# Politeitonsirene_V1.net
KiCad netlist of a schematic drawn in EAGLE
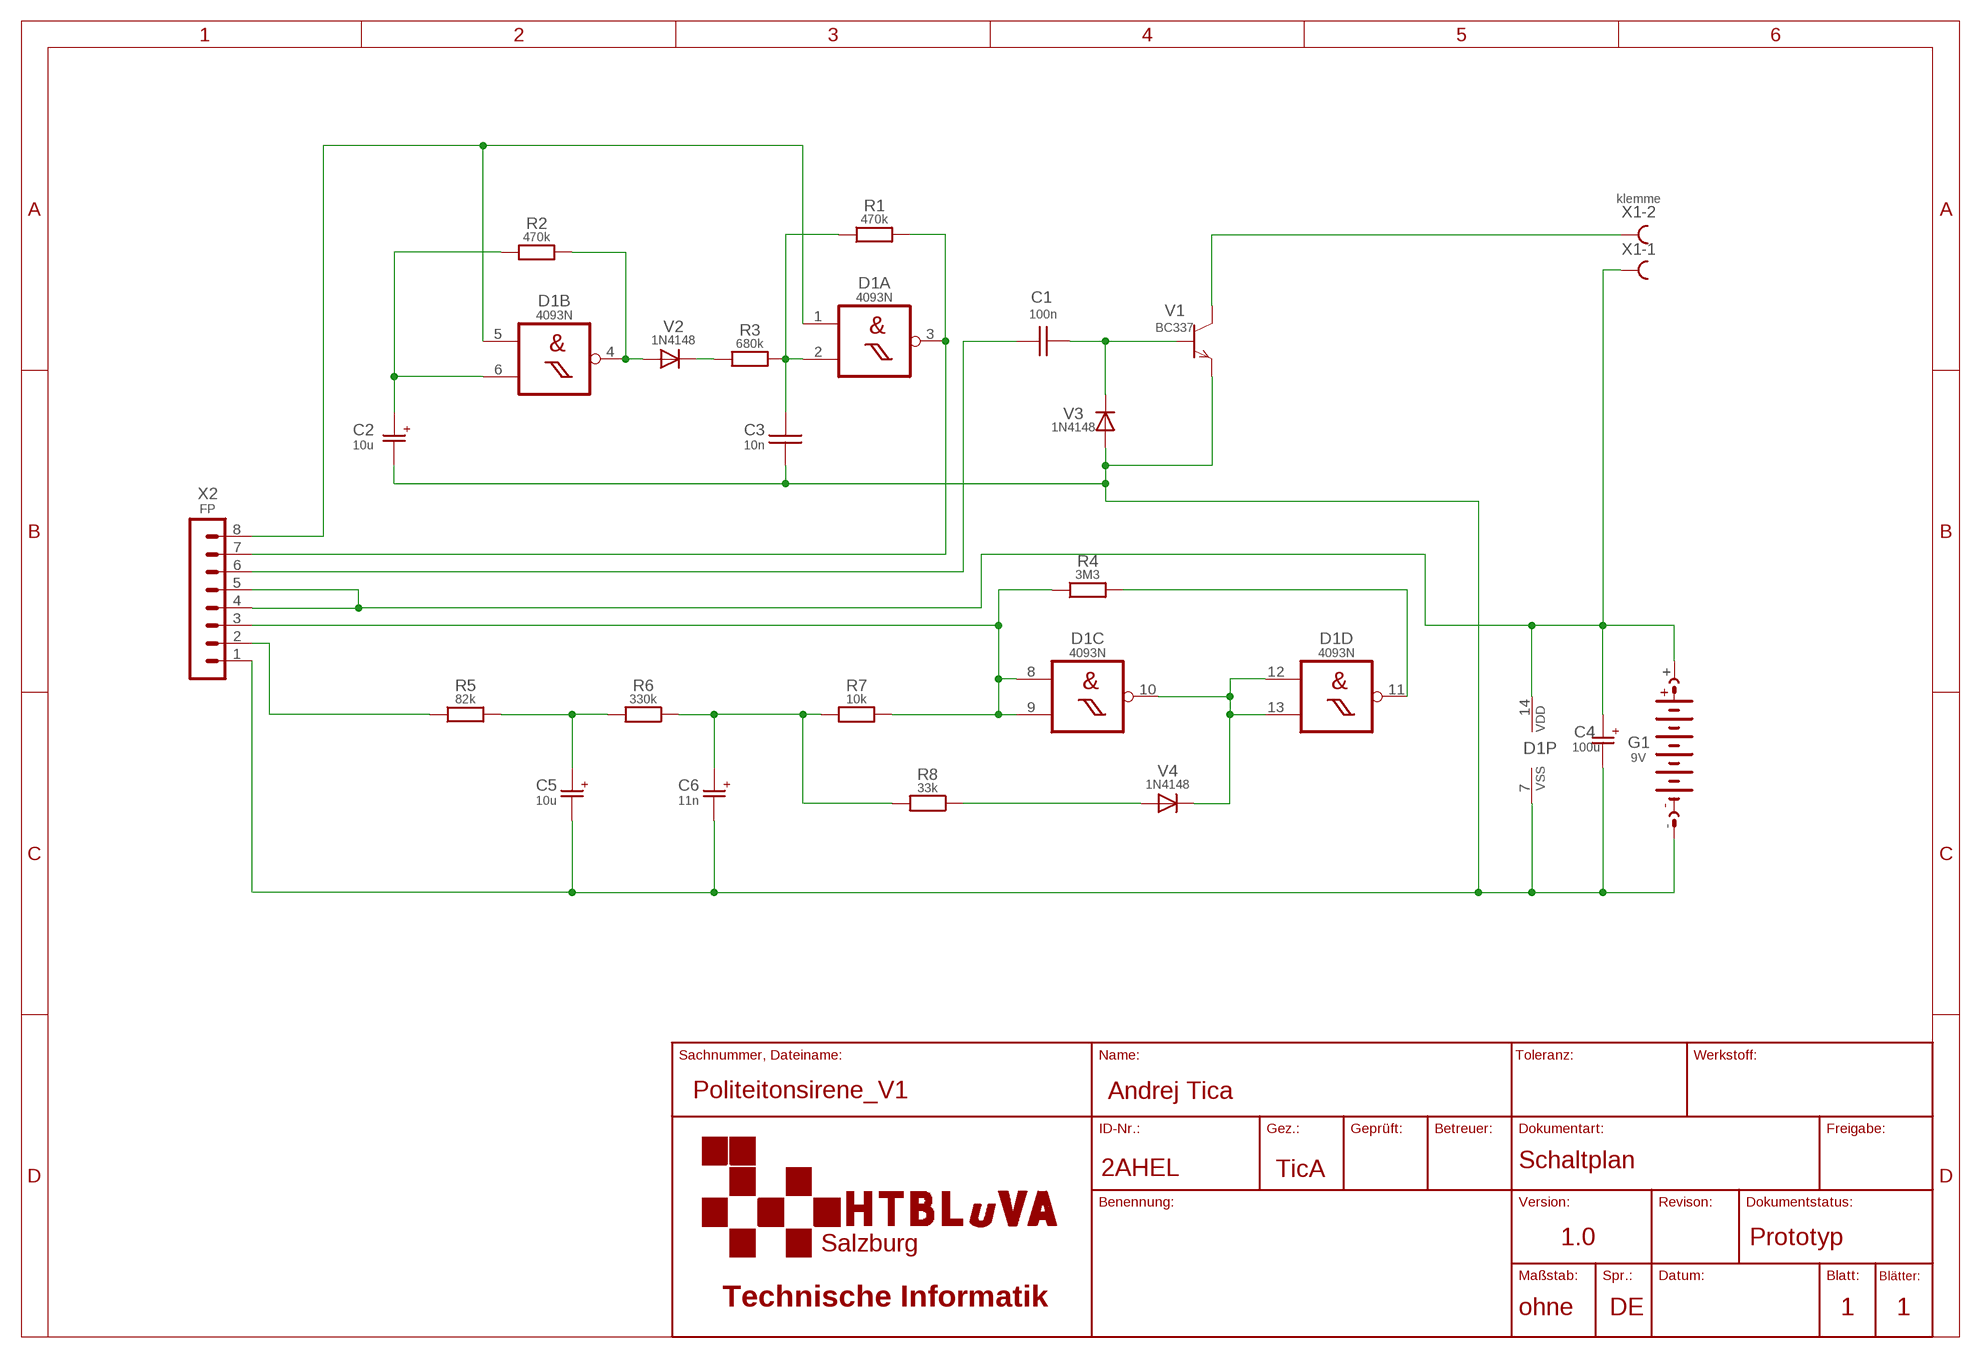
[diagram p0: schematic, sheet 1]

(export (version "E")
  (design (tool "Eeschema 10.0.6"))
  (components
    (comp (ref "C1")
      (value "100n")
      (footprint "eagle-import:C1206")
      (libsource (lib "eagle-import") (part "C-V_C1206"))
    )
    (comp (ref "C2")
      (value "10u")
      (footprint "eagle-import:E2,5-5")
      (libsource (lib "eagle-import") (part "CPOL-V_E2.5-5"))
    )
    (comp (ref "C3")
      (value "10n")
      (footprint "eagle-import:C050-024X044")
      (libsource (lib "eagle-import") (part "rcl_TicA_C-V_050-024X044"))
    )
    (comp (ref "C4")
      (value "100u")
      (footprint "eagle-import:E2,5-6")
      (libsource (lib "eagle-import") (part "CPOL-V_E2.5-6"))
    )
    (comp (ref "C5")
      (value "10u")
      (footprint "eagle-import:E2,5-5")
      (libsource (lib "eagle-import") (part "CPOL-V_E2.5-5"))
    )
    (comp (ref "C6")
      (value "11n")
      (footprint "eagle-import:E2,5-5")
      (libsource (lib "eagle-import") (part "CPOL-V_E2.5-5"))
    )
    (comp (ref "D1")
      (value "4093N")
      (footprint "eagle-import:DIL14")
      (libsource (lib "eagle-import") (part "4093N"))
    )
    (comp (ref "G1")
      (value "9V")
      (footprint "eagle-import:AB9V")
      (libsource (lib "eagle-import") (part "BATCLIP-9V-V_9V"))
    )
    (comp (ref "R1")
      (value "470k")
      (footprint "eagle-import:R2512")
      (libsource (lib "eagle-import") (part "R-H_R2512"))
    )
    (comp (ref "R2")
      (value "470k")
      (footprint "eagle-import:R2512")
      (libsource (lib "eagle-import") (part "R-H_R2512"))
    )
    (comp (ref "R3")
      (value "680k")
      (footprint "eagle-import:R2512")
      (libsource (lib "eagle-import") (part "R-H_R2512"))
    )
    (comp (ref "R4")
      (value "3M3")
      (footprint "eagle-import:R2512")
      (libsource (lib "eagle-import") (part "R-H_R2512"))
    )
    (comp (ref "R5")
      (value "82k")
      (footprint "eagle-import:R2512")
      (libsource (lib "eagle-import") (part "R-H_R2512"))
    )
    (comp (ref "R6")
      (value "330k")
      (footprint "eagle-import:R2512")
      (libsource (lib "eagle-import") (part "R-H_R2512"))
    )
    (comp (ref "R7")
      (value "10k")
      (footprint "eagle-import:R2512")
      (libsource (lib "eagle-import") (part "R-H_R2512"))
    )
    (comp (ref "R8")
      (value "33k")
      (footprint "eagle-import:R2512")
      (libsource (lib "eagle-import") (part "R-H_R2512"))
    )
    (comp (ref "V1")
      (value "BC337")
      (footprint "eagle-import:TO92")
      (libsource (lib "eagle-import") (part "BC337"))
    )
    (comp (ref "V2")
      (value "1N4148")
      (footprint "eagle-import:DO35-7")
      (libsource (lib "eagle-import") (part "1N4148_DO35-7"))
    )
    (comp (ref "V3")
      (value "1N4148")
      (footprint "eagle-import:DO35-7")
      (libsource (lib "eagle-import") (part "1N4148_DO35-7"))
    )
    (comp (ref "V4")
      (value "1N4148")
      (footprint "eagle-import:DO35-7")
      (libsource (lib "eagle-import") (part "1N4148_DO35-7"))
    )
    (comp (ref "X1")
      (value "klemme")
      (footprint "eagle-import:AK500_2")
      (libsource (lib "eagle-import") (part "AK500/2"))
    )
    (comp (ref "X2")
      (value "FP")
      (footprint "eagle-import:MA08-1")
      (libsource (lib "eagle-import") (part "MA08-1"))
    )
  )
  (nets
    (net (code "1") (name "Net-(C1-Pad2)") (class "Default")
      (node (ref "C1") (pin "2") (pinfunction "2_2") (pintype "passive"))
      (node (ref "X2") (pin "6") (pinfunction "6_6") (pintype "passive"))
    )
    (net (code "2") (name "Net-(C5-Pad+)") (class "Default")
      (node (ref "C5") (pin "+") (pinfunction "+_+") (pintype "passive"))
      (node (ref "R5") (pin "2") (pinfunction "2_2") (pintype "passive"))
      (node (ref "R6") (pin "2") (pinfunction "2_2") (pintype "passive"))
    )
    (net (code "3") (name "Net-(C6-Pad+)") (class "Default")
      (node (ref "C6") (pin "+") (pinfunction "+_+") (pintype "passive"))
      (node (ref "R6") (pin "1") (pinfunction "1_1") (pintype "passive"))
      (node (ref "R7") (pin "2") (pinfunction "2_2") (pintype "passive"))
      (node (ref "R8") (pin "2") (pinfunction "2_2") (pintype "passive"))
    )
    (net (code "4") (name "Net-(D1A-I0)") (class "Default")
      (node (ref "D1") (pin "1") (pinfunction "I0_1") (pintype "input"))
      (node (ref "D1") (pin "5") (pinfunction "I0_5") (pintype "input"))
      (node (ref "X2") (pin "8") (pinfunction "8_8") (pintype "passive"))
    )
    (net (code "5") (name "Net-(D1A-I1)") (class "Default")
      (node (ref "C3") (pin "1") (pinfunction "1_1") (pintype "passive"))
      (node (ref "D1") (pin "2") (pinfunction "I1_2") (pintype "input"))
      (node (ref "R1") (pin "1") (pinfunction "1_1") (pintype "passive"))
      (node (ref "R3") (pin "2") (pinfunction "2_2") (pintype "passive"))
    )
    (net (code "6") (name "Net-(D1A-O)") (class "Default")
      (node (ref "D1") (pin "3") (pinfunction "O_3") (pintype "output"))
      (node (ref "R1") (pin "2") (pinfunction "2_2") (pintype "passive"))
      (node (ref "X2") (pin "7") (pinfunction "7_7") (pintype "passive"))
    )
    (net (code "7") (name "Net-(D1B-I1)") (class "Default")
      (node (ref "C2") (pin "+") (pinfunction "+_+") (pintype "passive"))
      (node (ref "D1") (pin "6") (pinfunction "I1_6") (pintype "input"))
      (node (ref "R2") (pin "1") (pinfunction "1_1") (pintype "passive"))
    )
    (net (code "8") (name "Net-(D1B-O)") (class "Default")
      (node (ref "D1") (pin "4") (pinfunction "O_4") (pintype "output"))
      (node (ref "R2") (pin "2") (pinfunction "2_2") (pintype "passive"))
      (node (ref "V2") (pin "A") (pinfunction "A_A") (pintype "passive"))
    )
    (net (code "9") (name "Net-(D1C-I0)") (class "Default")
      (node (ref "D1") (pin "8") (pinfunction "I0_8") (pintype "input"))
      (node (ref "D1") (pin "9") (pinfunction "I1_9") (pintype "input"))
      (node (ref "R4") (pin "1") (pinfunction "1_1") (pintype "passive"))
      (node (ref "R7") (pin "1") (pinfunction "1_1") (pintype "passive"))
      (node (ref "X2") (pin "3") (pinfunction "3_3") (pintype "passive"))
    )
    (net (code "10") (name "Net-(D1C-O)") (class "Default")
      (node (ref "D1") (pin "10") (pinfunction "O_10") (pintype "output"))
      (node (ref "D1") (pin "12") (pinfunction "I0_12") (pintype "input"))
      (node (ref "D1") (pin "13") (pinfunction "I1_13") (pintype "input"))
      (node (ref "V4") (pin "C") (pinfunction "C_C") (pintype "passive"))
    )
    (net (code "11") (name "Net-(D1D-O)") (class "Default")
      (node (ref "D1") (pin "11") (pinfunction "O_11") (pintype "output"))
      (node (ref "R4") (pin "2") (pinfunction "2_2") (pintype "passive"))
    )
    (net (code "12") (name "Net-(D1E-VDD)") (class "Default")
      (node (ref "C4") (pin "+") (pinfunction "+_+") (pintype "passive"))
      (node (ref "D1") (pin "14") (pinfunction "VDD_14") (pintype "power_in"))
      (node (ref "G1") (pin "+") (pinfunction "+_+") (pintype "passive"))
      (node (ref "X1") (pin "1") (pinfunction "KL_1") (pintype "passive"))
      (node (ref "X2") (pin "4") (pinfunction "4_4") (pintype "passive"))
      (node (ref "X2") (pin "5") (pinfunction "5_5") (pintype "passive"))
    )
    (net (code "13") (name "Net-(D1E-VSS)") (class "Default")
      (node (ref "C2") (pin "-") (pinfunction "-_-") (pintype "passive"))
      (node (ref "C3") (pin "2") (pinfunction "2_2") (pintype "passive"))
      (node (ref "C4") (pin "-") (pinfunction "-_-") (pintype "passive"))
      (node (ref "C5") (pin "-") (pinfunction "-_-") (pintype "passive"))
      (node (ref "C6") (pin "-") (pinfunction "-_-") (pintype "passive"))
      (node (ref "D1") (pin "7") (pinfunction "VSS_7") (pintype "power_in"))
      (node (ref "G1") (pin "-") (pinfunction "-_-") (pintype "passive"))
      (node (ref "V1") (pin "1") (pinfunction "E_1") (pintype "passive"))
      (node (ref "V3") (pin "A") (pinfunction "A_A") (pintype "passive"))
      (node (ref "X2") (pin "1") (pinfunction "1_1") (pintype "passive"))
    )
    (net (code "14") (name "Net-(R3-Pad1)") (class "Default")
      (node (ref "R3") (pin "1") (pinfunction "1_1") (pintype "passive"))
      (node (ref "V2") (pin "C") (pinfunction "C_C") (pintype "passive"))
    )
    (net (code "15") (name "Net-(R5-Pad1)") (class "Default")
      (node (ref "R5") (pin "1") (pinfunction "1_1") (pintype "passive"))
      (node (ref "X2") (pin "2") (pinfunction "2_2") (pintype "passive"))
    )
    (net (code "16") (name "Net-(R8-Pad1)") (class "Default")
      (node (ref "R8") (pin "1") (pinfunction "1_1") (pintype "passive"))
      (node (ref "V4") (pin "A") (pinfunction "A_A") (pintype "passive"))
    )
    (net (code "17") (name "Net-(V1-B)") (class "Default")
      (node (ref "C1") (pin "1") (pinfunction "1_1") (pintype "passive"))
      (node (ref "V1") (pin "2") (pinfunction "B_2") (pintype "passive"))
      (node (ref "V3") (pin "C") (pinfunction "C_C") (pintype "passive"))
    )
    (net (code "18") (name "Net-(V1-C)") (class "Default")
      (node (ref "V1") (pin "3") (pinfunction "C_3") (pintype "passive"))
      (node (ref "X1") (pin "2") (pinfunction "KL_2") (pintype "passive"))
    )
  )
)
